# 09_FPGA_banks_5_6_7_8.net
KiCad netlist of a schematic drawn in Altium Designer
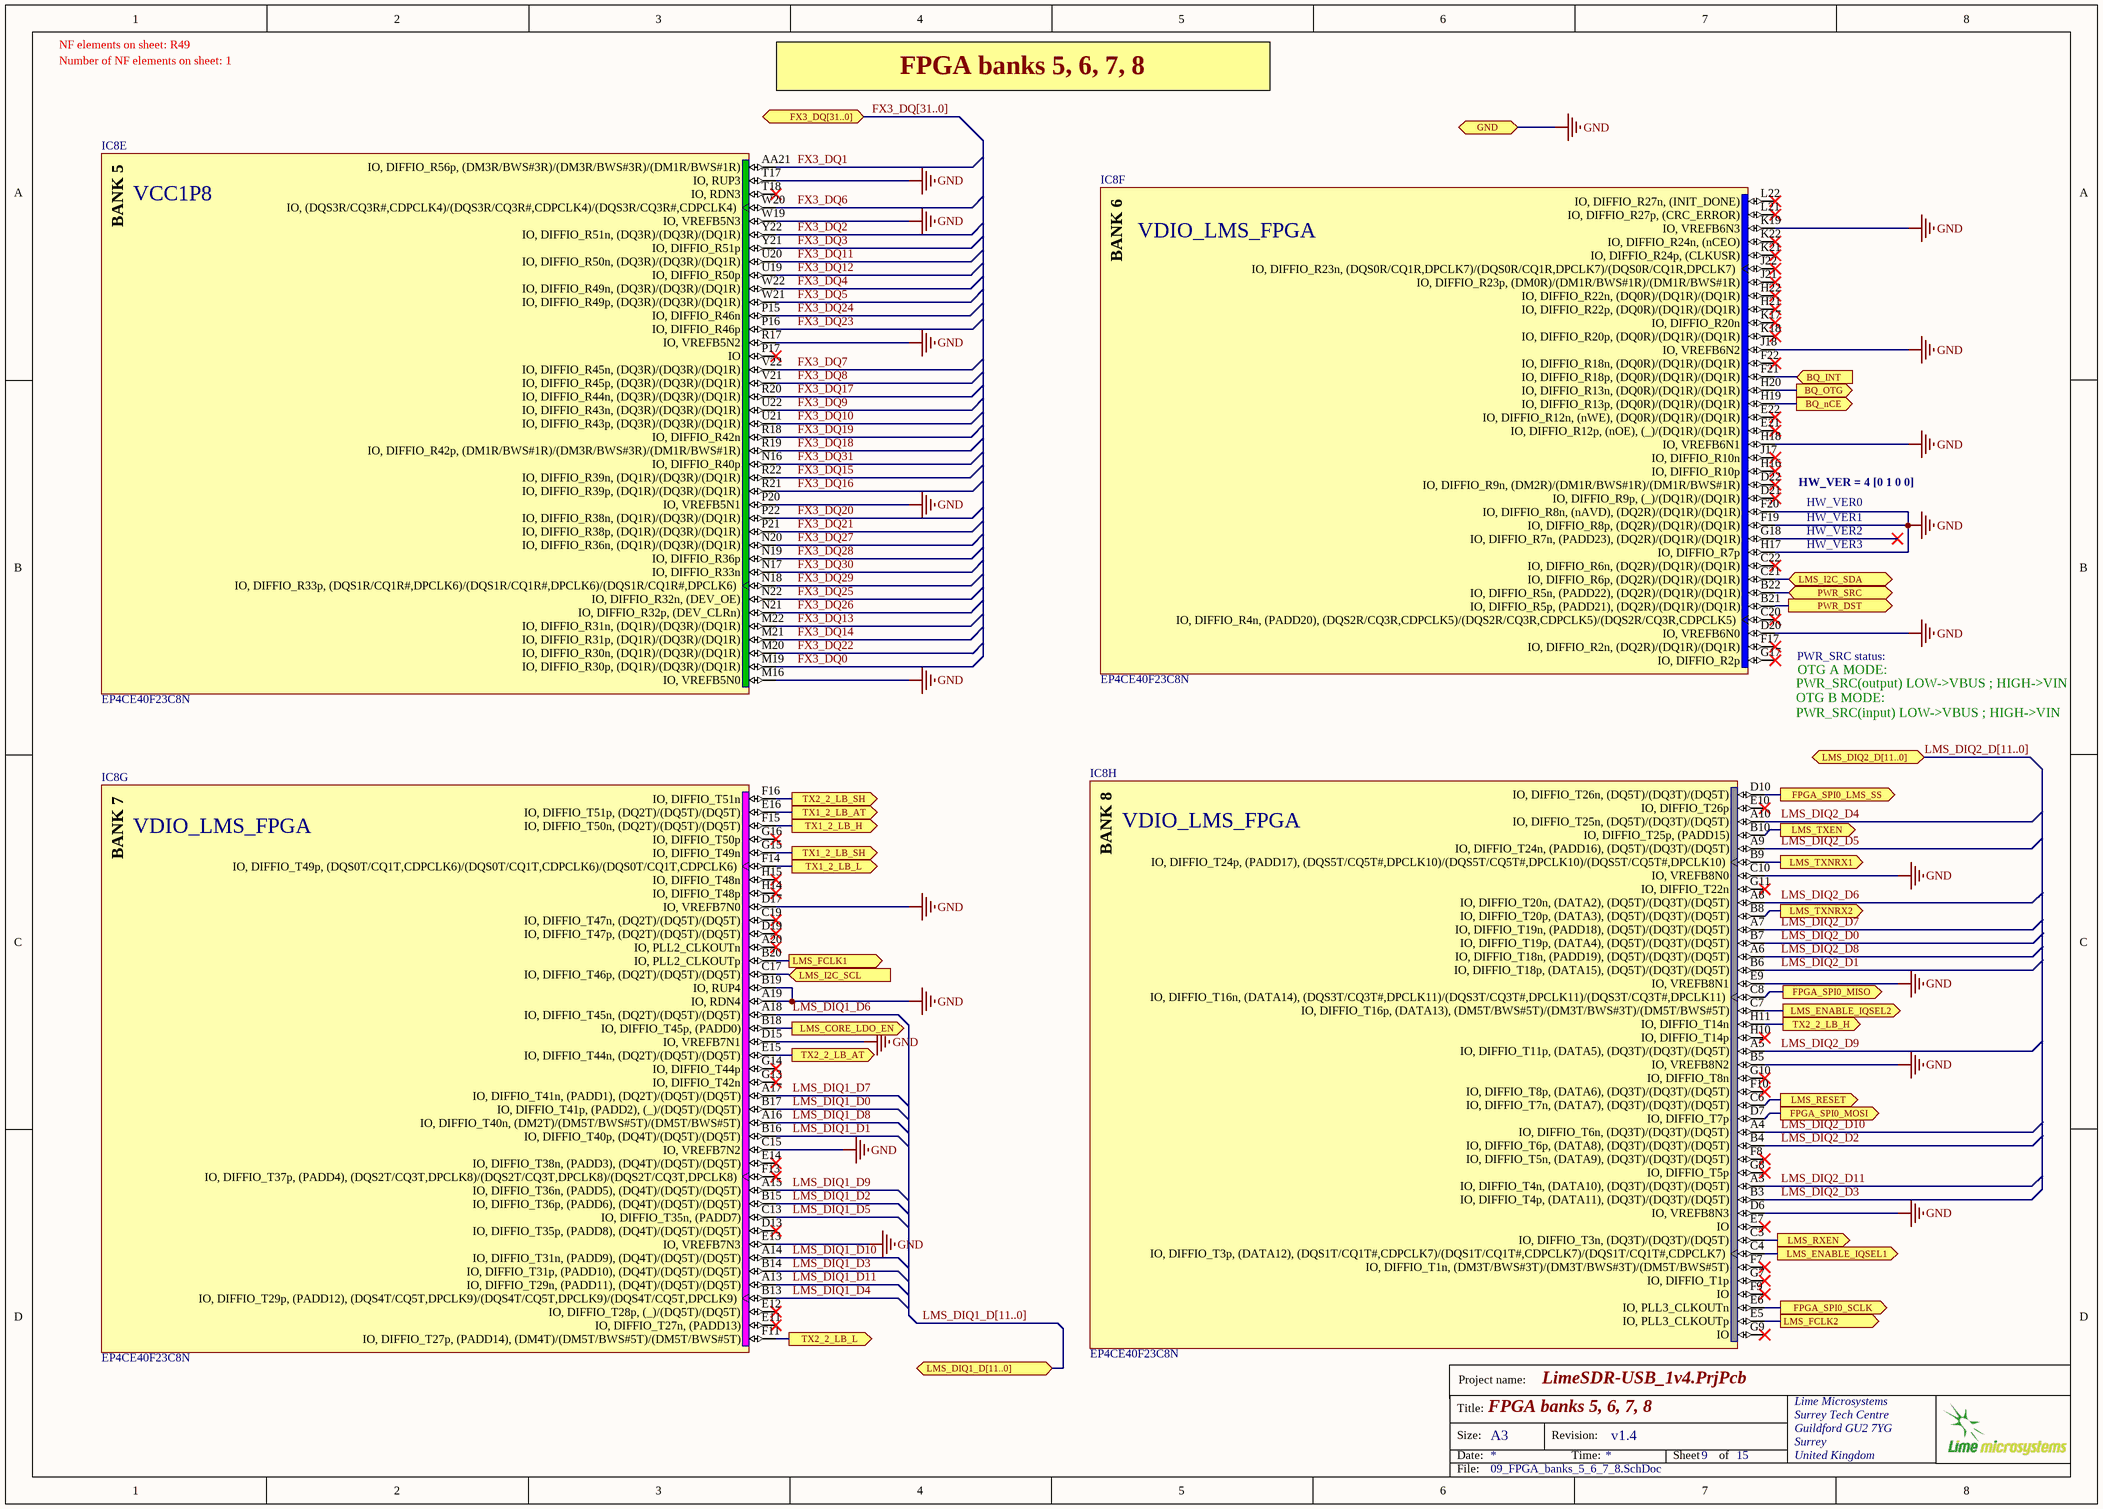
[diagram p0: 09_FPGA_banks_5_6_7_8.SchDoc]

(export (version "E")
  (design (tool "Eeschema 10.0.6"))
  (components
    (comp (ref "IC8")
      (value "EP4CE40F23C8N")
      (footprint "FBGA484_A-240")
      (description "IC FPGA 328 I/O 484FBGA")
      (fields (field (name "MANUFACTURER") "Altera"))
      (libsource (lib "LimeMicroAltiumLib_schLib") (part "EP4CE40F23C7N"))
    )
  )
  (nets
    (net (code "1") (name "/BQ_INT") (class "Default")
      (node (ref "IC8") (pin "F21") (pinfunction "IO,_DIFFIO_R18p,_(DQ0R)/(DQ1R)/(DQ1R)_F21") (pintype "bidirectional"))
    )
    (net (code "2") (name "/BQ_OTG") (class "Default")
      (node (ref "IC8") (pin "H20") (pinfunction "IO,_DIFFIO_R13n,_(DQ0R)/(DQ1R)/(DQ1R)_H20") (pintype "bidirectional"))
    )
    (net (code "3") (name "/BQ_nCE") (class "Default")
      (node (ref "IC8") (pin "H19") (pinfunction "IO,_DIFFIO_R13p,_(DQ0R)/(DQ1R)/(DQ1R)_H19") (pintype "bidirectional"))
    )
    (net (code "4") (name "/FPGA_SPI0_LMS_SS") (class "Default")
      (node (ref "IC8") (pin "D10") (pinfunction "IO,_DIFFIO_T26n,_(DQ5T)/(DQ3T)/(DQ5T)_D10") (pintype "bidirectional"))
    )
    (net (code "5") (name "/FPGA_SPI0_MISO") (class "Default")
      (node (ref "IC8") (pin "C8") (pinfunction "IO,_DIFFIO_T16n,_(DATA14),_(DQS3T/CQ3T#,DPCLK11)/(DQS3T/CQ3T#,DPCLK11)/(DQS3T/CQ3T#,DPCLK11)_C8") (pintype "bidirectional"))
    )
    (net (code "6") (name "/FPGA_SPI0_MOSI") (class "Default")
      (node (ref "IC8") (pin "D7") (pinfunction "IO,_DIFFIO_T7p_D7") (pintype "bidirectional"))
    )
    (net (code "7") (name "/FPGA_SPI0_SCLK") (class "Default")
      (node (ref "IC8") (pin "E6") (pinfunction "IO,_PLL3_CLKOUTn_E6") (pintype "bidirectional"))
    )
    (net (code "8") (name "/FX3_DQ0") (class "Default")
      (node (ref "IC8") (pin "M19") (pinfunction "IO,_DIFFIO_R30p,_(DQ1R)/(DQ3R)/(DQ1R)_M19") (pintype "bidirectional"))
    )
    (net (code "9") (name "/FX3_DQ1") (class "Default")
      (node (ref "IC8") (pin "AA21") (pinfunction "IO,_DIFFIO_R56p,_(DM3R/BWS#3R)/(DM3R/BWS#3R)/(DM1R/BWS#1R)_AA21") (pintype "bidirectional"))
    )
    (net (code "10") (name "/FX3_DQ2") (class "Default")
      (node (ref "IC8") (pin "Y22") (pinfunction "IO,_DIFFIO_R51n,_(DQ3R)/(DQ3R)/(DQ1R)_Y22") (pintype "bidirectional"))
    )
    (net (code "11") (name "/FX3_DQ3") (class "Default")
      (node (ref "IC8") (pin "Y21") (pinfunction "IO,_DIFFIO_R51p_Y21") (pintype "bidirectional"))
    )
    (net (code "12") (name "/FX3_DQ4") (class "Default")
      (node (ref "IC8") (pin "W22") (pinfunction "IO,_DIFFIO_R49n,_(DQ3R)/(DQ3R)/(DQ1R)_W22") (pintype "bidirectional"))
    )
    (net (code "13") (name "/FX3_DQ5") (class "Default")
      (node (ref "IC8") (pin "W21") (pinfunction "IO,_DIFFIO_R49p,_(DQ3R)/(DQ3R)/(DQ1R)_W21") (pintype "bidirectional"))
    )
    (net (code "14") (name "/FX3_DQ6") (class "Default")
      (node (ref "IC8") (pin "W20") (pinfunction "IO,_(DQS3R/CQ3R#,CDPCLK4)/(DQS3R/CQ3R#,CDPCLK4)/(DQS3R/CQ3R#,CDPCLK4)_W20") (pintype "bidirectional"))
    )
    (net (code "15") (name "/FX3_DQ7") (class "Default")
      (node (ref "IC8") (pin "V22") (pinfunction "IO,_DIFFIO_R45n,_(DQ3R)/(DQ3R)/(DQ1R)_V22") (pintype "bidirectional"))
    )
    (net (code "16") (name "/FX3_DQ8") (class "Default")
      (node (ref "IC8") (pin "V21") (pinfunction "IO,_DIFFIO_R45p,_(DQ3R)/(DQ3R)/(DQ1R)_V21") (pintype "bidirectional"))
    )
    (net (code "17") (name "/FX3_DQ9") (class "Default")
      (node (ref "IC8") (pin "U22") (pinfunction "IO,_DIFFIO_R43n,_(DQ3R)/(DQ3R)/(DQ1R)_U22") (pintype "bidirectional"))
    )
    (net (code "18") (name "/FX3_DQ10") (class "Default")
      (node (ref "IC8") (pin "U21") (pinfunction "IO,_DIFFIO_R43p,_(DQ3R)/(DQ3R)/(DQ1R)_U21") (pintype "bidirectional"))
    )
    (net (code "19") (name "/FX3_DQ11") (class "Default")
      (node (ref "IC8") (pin "U20") (pinfunction "IO,_DIFFIO_R50n,_(DQ3R)/(DQ3R)/(DQ1R)_U20") (pintype "bidirectional"))
    )
    (net (code "20") (name "/FX3_DQ12") (class "Default")
      (node (ref "IC8") (pin "U19") (pinfunction "IO,_DIFFIO_R50p_U19") (pintype "bidirectional"))
    )
    (net (code "21") (name "/FX3_DQ13") (class "Default")
      (node (ref "IC8") (pin "M22") (pinfunction "IO,_DIFFIO_R31n,_(DQ1R)/(DQ3R)/(DQ1R)_M22") (pintype "bidirectional"))
    )
    (net (code "22") (name "/FX3_DQ14") (class "Default")
      (node (ref "IC8") (pin "M21") (pinfunction "IO,_DIFFIO_R31p,_(DQ1R)/(DQ3R)/(DQ1R)_M21") (pintype "bidirectional"))
    )
    (net (code "23") (name "/FX3_DQ15") (class "Default")
      (node (ref "IC8") (pin "R22") (pinfunction "IO,_DIFFIO_R39n,_(DQ1R)/(DQ3R)/(DQ1R)_R22") (pintype "bidirectional"))
    )
    (net (code "24") (name "/FX3_DQ16") (class "Default")
      (node (ref "IC8") (pin "R21") (pinfunction "IO,_DIFFIO_R39p,_(DQ1R)/(DQ3R)/(DQ1R)_R21") (pintype "bidirectional"))
    )
    (net (code "25") (name "/FX3_DQ17") (class "Default")
      (node (ref "IC8") (pin "R20") (pinfunction "IO,_DIFFIO_R44n,_(DQ3R)/(DQ3R)/(DQ1R)_R20") (pintype "bidirectional"))
    )
    (net (code "26") (name "/FX3_DQ18") (class "Default")
      (node (ref "IC8") (pin "R19") (pinfunction "IO,_DIFFIO_R42p,_(DM1R/BWS#1R)/(DM3R/BWS#3R)/(DM1R/BWS#1R)_R19") (pintype "bidirectional"))
    )
    (net (code "27") (name "/FX3_DQ19") (class "Default")
      (node (ref "IC8") (pin "R18") (pinfunction "IO,_DIFFIO_R42n_R18") (pintype "bidirectional"))
    )
    (net (code "28") (name "/FX3_DQ20") (class "Default")
      (node (ref "IC8") (pin "P22") (pinfunction "IO,_DIFFIO_R38n,_(DQ1R)/(DQ3R)/(DQ1R)_P22") (pintype "bidirectional"))
    )
    (net (code "29") (name "/FX3_DQ21") (class "Default")
      (node (ref "IC8") (pin "P21") (pinfunction "IO,_DIFFIO_R38p,_(DQ1R)/(DQ3R)/(DQ1R)_P21") (pintype "bidirectional"))
    )
    (net (code "30") (name "/FX3_DQ22") (class "Default")
      (node (ref "IC8") (pin "M20") (pinfunction "IO,_DIFFIO_R30n,_(DQ1R)/(DQ3R)/(DQ1R)_M20") (pintype "bidirectional"))
    )
    (net (code "31") (name "/FX3_DQ23") (class "Default")
      (node (ref "IC8") (pin "P16") (pinfunction "IO,_DIFFIO_R46p_P16") (pintype "bidirectional"))
    )
    (net (code "32") (name "/FX3_DQ24") (class "Default")
      (node (ref "IC8") (pin "P15") (pinfunction "IO,_DIFFIO_R46n_P15") (pintype "bidirectional"))
    )
    (net (code "33") (name "/FX3_DQ25") (class "Default")
      (node (ref "IC8") (pin "N22") (pinfunction "IO,_DIFFIO_R32n,_(DEV_OE)_N22") (pintype "bidirectional"))
    )
    (net (code "34") (name "/FX3_DQ26") (class "Default")
      (node (ref "IC8") (pin "N21") (pinfunction "IO,_DIFFIO_R32p,_(DEV_CLRn)_N21") (pintype "bidirectional"))
    )
    (net (code "35") (name "/FX3_DQ27") (class "Default")
      (node (ref "IC8") (pin "N20") (pinfunction "IO,_DIFFIO_R36n,_(DQ1R)/(DQ3R)/(DQ1R)_N20") (pintype "bidirectional"))
    )
    (net (code "36") (name "/FX3_DQ28") (class "Default")
      (node (ref "IC8") (pin "N19") (pinfunction "IO,_DIFFIO_R36p_N19") (pintype "bidirectional"))
    )
    (net (code "37") (name "/FX3_DQ29") (class "Default")
      (node (ref "IC8") (pin "N18") (pinfunction "IO,_DIFFIO_R33p,_(DQS1R/CQ1R#,DPCLK6)/(DQS1R/CQ1R#,DPCLK6)/(DQS1R/CQ1R#,DPCLK6)_N18") (pintype "bidirectional"))
    )
    (net (code "38") (name "/FX3_DQ30") (class "Default")
      (node (ref "IC8") (pin "N17") (pinfunction "IO,_DIFFIO_R33n_N17") (pintype "bidirectional"))
    )
    (net (code "39") (name "/FX3_DQ31") (class "Default")
      (node (ref "IC8") (pin "N16") (pinfunction "IO,_DIFFIO_R40p_N16") (pintype "bidirectional"))
    )
    (net (code "41") (name "/LMS_CORE_LDO_EN") (class "Default")
      (node (ref "IC8") (pin "B18") (pinfunction "IO,_DIFFIO_T45p,_(PADD0)_B18") (pintype "bidirectional"))
    )
    (net (code "42") (name "/LMS_DIQ1_D0") (class "Default")
      (node (ref "IC8") (pin "B17") (pinfunction "IO,_DIFFIO_T41p,_(PADD2),_(_)/(DQ5T)/(DQ5T)_B17") (pintype "bidirectional"))
    )
    (net (code "43") (name "/LMS_DIQ1_D1") (class "Default")
      (node (ref "IC8") (pin "B16") (pinfunction "IO,_DIFFIO_T40p,_(DQ4T)/(DQ5T)/(DQ5T)_B16") (pintype "bidirectional"))
    )
    (net (code "44") (name "/LMS_DIQ1_D2") (class "Default")
      (node (ref "IC8") (pin "B15") (pinfunction "IO,_DIFFIO_T36p,_(PADD6),_(DQ4T)/(DQ5T)/(DQ5T)_B15") (pintype "bidirectional"))
    )
    (net (code "45") (name "/LMS_DIQ1_D3") (class "Default")
      (node (ref "IC8") (pin "B14") (pinfunction "IO,_DIFFIO_T31p,_(PADD10),_(DQ4T)/(DQ5T)/(DQ5T)_B14") (pintype "bidirectional"))
    )
    (net (code "46") (name "/LMS_DIQ1_D4") (class "Default")
      (node (ref "IC8") (pin "B13") (pinfunction "IO,_DIFFIO_T29p,_(PADD12),_(DQS4T/CQ5T,DPCLK9)/(DQS4T/CQ5T,DPCLK9)/(DQS4T/CQ5T,DPCLK9)_B13") (pintype "bidirectional"))
    )
    (net (code "47") (name "/LMS_DIQ1_D5") (class "Default")
      (node (ref "IC8") (pin "C13") (pinfunction "IO,_DIFFIO_T35n,_(PADD7)_C13") (pintype "bidirectional"))
    )
    (net (code "48") (name "/LMS_DIQ1_D6") (class "Default")
      (node (ref "IC8") (pin "A18") (pinfunction "IO,_DIFFIO_T45n,_(DQ2T)/(DQ5T)/(DQ5T)_A18") (pintype "bidirectional"))
    )
    (net (code "49") (name "/LMS_DIQ1_D7") (class "Default")
      (node (ref "IC8") (pin "A17") (pinfunction "IO,_DIFFIO_T41n,_(PADD1),_(DQ2T)/(DQ5T)/(DQ5T)_A17") (pintype "bidirectional"))
    )
    (net (code "50") (name "/LMS_DIQ1_D8") (class "Default")
      (node (ref "IC8") (pin "A16") (pinfunction "IO,_DIFFIO_T40n,_(DM2T)/(DM5T/BWS#5T)/(DM5T/BWS#5T)_A16") (pintype "bidirectional"))
    )
    (net (code "51") (name "/LMS_DIQ1_D9") (class "Default")
      (node (ref "IC8") (pin "A15") (pinfunction "IO,_DIFFIO_T36n,_(PADD5),_(DQ4T)/(DQ5T)/(DQ5T)_A15") (pintype "bidirectional"))
    )
    (net (code "52") (name "/LMS_DIQ1_D10") (class "Default")
      (node (ref "IC8") (pin "A14") (pinfunction "IO,_DIFFIO_T31n,_(PADD9),_(DQ4T)/(DQ5T)/(DQ5T)_A14") (pintype "bidirectional"))
    )
    (net (code "53") (name "/LMS_DIQ1_D11") (class "Default")
      (node (ref "IC8") (pin "A13") (pinfunction "IO,_DIFFIO_T29n,_(PADD11),_(DQ4T)/(DQ5T)/(DQ5T)_A13") (pintype "bidirectional"))
    )
    (net (code "55") (name "/LMS_DIQ2_D0") (class "Default")
      (node (ref "IC8") (pin "B7") (pinfunction "IO,_DIFFIO_T19p,_(DATA4),_(DQ5T)/(DQ3T)/(DQ5T)_B7") (pintype "bidirectional"))
    )
    (net (code "56") (name "/LMS_DIQ2_D1") (class "Default")
      (node (ref "IC8") (pin "B6") (pinfunction "IO,_DIFFIO_T18p,_(DATA15),_(DQ5T)/(DQ3T)/(DQ5T)_B6") (pintype "bidirectional"))
    )
    (net (code "57") (name "/LMS_DIQ2_D2") (class "Default")
      (node (ref "IC8") (pin "B4") (pinfunction "IO,_DIFFIO_T6p,_(DATA8),_(DQ3T)/(DQ3T)/(DQ5T)_B4") (pintype "bidirectional"))
    )
    (net (code "58") (name "/LMS_DIQ2_D3") (class "Default")
      (node (ref "IC8") (pin "B3") (pinfunction "IO,_DIFFIO_T4p,_(DATA11),_(DQ3T)/(DQ3T)/(DQ5T)_B3") (pintype "bidirectional"))
    )
    (net (code "59") (name "/LMS_DIQ2_D4") (class "Default")
      (node (ref "IC8") (pin "A10") (pinfunction "IO,_DIFFIO_T25n,_(DQ5T)/(DQ3T)/(DQ5T)_A10") (pintype "bidirectional"))
    )
    (net (code "60") (name "/LMS_DIQ2_D5") (class "Default")
      (node (ref "IC8") (pin "A9") (pinfunction "IO,_DIFFIO_T24n,_(PADD16),_(DQ5T)/(DQ3T)/(DQ5T)_A9") (pintype "bidirectional"))
    )
    (net (code "61") (name "/LMS_DIQ2_D6") (class "Default")
      (node (ref "IC8") (pin "A8") (pinfunction "IO,_DIFFIO_T20n,_(DATA2),_(DQ5T)/(DQ3T)/(DQ5T)_A8") (pintype "bidirectional"))
    )
    (net (code "62") (name "/LMS_DIQ2_D7") (class "Default")
      (node (ref "IC8") (pin "A7") (pinfunction "IO,_DIFFIO_T19n,_(PADD18),_(DQ5T)/(DQ3T)/(DQ5T)_A7") (pintype "bidirectional"))
    )
    (net (code "63") (name "/LMS_DIQ2_D8") (class "Default")
      (node (ref "IC8") (pin "A6") (pinfunction "IO,_DIFFIO_T18n,_(PADD19),_(DQ5T)/(DQ3T)/(DQ5T)_A6") (pintype "bidirectional"))
    )
    (net (code "64") (name "/LMS_DIQ2_D9") (class "Default")
      (node (ref "IC8") (pin "A5") (pinfunction "IO,_DIFFIO_T11p,_(DATA5),_(DQ3T)/(DQ3T)/(DQ5T)_A5") (pintype "bidirectional"))
    )
    (net (code "65") (name "/LMS_DIQ2_D10") (class "Default")
      (node (ref "IC8") (pin "A4") (pinfunction "IO,_DIFFIO_T6n,_(DQ3T)/(DQ3T)/(DQ5T)_A4") (pintype "bidirectional"))
    )
    (net (code "66") (name "/LMS_DIQ2_D11") (class "Default")
      (node (ref "IC8") (pin "A3") (pinfunction "IO,_DIFFIO_T4n,_(DATA10),_(DQ3T)/(DQ3T)/(DQ5T)_A3") (pintype "bidirectional"))
    )
    (net (code "68") (name "/LMS_ENABLE_IQSEL1") (class "Default")
      (node (ref "IC8") (pin "C4") (pinfunction "IO,_DIFFIO_T3p,_(DATA12),_(DQS1T/CQ1T#,CDPCLK7)/(DQS1T/CQ1T#,CDPCLK7)/(DQS1T/CQ1T#,CDPCLK7)_C4") (pintype "bidirectional"))
    )
    (net (code "69") (name "/LMS_ENABLE_IQSEL2") (class "Default")
      (node (ref "IC8") (pin "C7") (pinfunction "IO,_DIFFIO_T16p,_(DATA13),_(DM5T/BWS#5T)/(DM3T/BWS#3T)/(DM5T/BWS#5T)_C7") (pintype "bidirectional"))
    )
    (net (code "70") (name "/LMS_FCLK1") (class "Default")
      (node (ref "IC8") (pin "B20") (pinfunction "IO,_PLL2_CLKOUTp_B20") (pintype "bidirectional"))
    )
    (net (code "71") (name "/LMS_FCLK2") (class "Default")
      (node (ref "IC8") (pin "E5") (pinfunction "IO,_PLL3_CLKOUTp_E5") (pintype "bidirectional"))
    )
    (net (code "72") (name "/LMS_I2C_SCL") (class "Default")
      (node (ref "IC8") (pin "C17") (pinfunction "IO,_DIFFIO_T46p,_(DQ2T)/(DQ5T)/(DQ5T)_C17") (pintype "bidirectional"))
    )
    (net (code "73") (name "/LMS_I2C_SDA") (class "Default")
      (node (ref "IC8") (pin "C21") (pinfunction "IO,_DIFFIO_R6p,_(DQ2R)/(DQ1R)/(DQ1R)_C21") (pintype "bidirectional"))
    )
    (net (code "74") (name "/LMS_RESET") (class "Default")
      (node (ref "IC8") (pin "C6") (pinfunction "IO,_DIFFIO_T7n,_(DATA7),_(DQ3T)/(DQ3T)/(DQ5T)_C6") (pintype "bidirectional"))
    )
    (net (code "75") (name "/LMS_RXEN") (class "Default")
      (node (ref "IC8") (pin "C3") (pinfunction "IO,_DIFFIO_T3n,_(DQ3T)/(DQ3T)/(DQ5T)_C3") (pintype "bidirectional"))
    )
    (net (code "76") (name "/LMS_TXEN") (class "Default")
      (node (ref "IC8") (pin "B10") (pinfunction "IO,_DIFFIO_T25p,_(PADD15)_B10") (pintype "bidirectional"))
    )
    (net (code "77") (name "/LMS_TXNRX1") (class "Default")
      (node (ref "IC8") (pin "B9") (pinfunction "IO,_DIFFIO_T24p,_(PADD17),_(DQS5T/CQ5T#,DPCLK10)/(DQS5T/CQ5T#,DPCLK10)/(DQS5T/CQ5T#,DPCLK10)_B9") (pintype "bidirectional"))
    )
    (net (code "78") (name "/LMS_TXNRX2") (class "Default")
      (node (ref "IC8") (pin "B8") (pinfunction "IO,_DIFFIO_T20p,_(DATA3),_(DQ5T)/(DQ3T)/(DQ5T)_B8") (pintype "bidirectional"))
    )
    (net (code "79") (name "/PWR_DST") (class "Default")
      (node (ref "IC8") (pin "B21") (pinfunction "IO,_DIFFIO_R5p,_(PADD21),_(DQ2R)/(DQ1R)/(DQ1R)_B21") (pintype "bidirectional"))
    )
    (net (code "80") (name "/PWR_SRC") (class "Default")
      (node (ref "IC8") (pin "B22") (pinfunction "IO,_DIFFIO_R5n,_(PADD22),_(DQ2R)/(DQ1R)/(DQ1R)_B22") (pintype "bidirectional"))
    )
    (net (code "81") (name "/TX1_2_LB_AT") (class "Default")
      (node (ref "IC8") (pin "E16") (pinfunction "IO,_DIFFIO_T51p,_(DQ2T)/(DQ5T)/(DQ5T)_E16") (pintype "bidirectional"))
    )
    (net (code "82") (name "/TX1_2_LB_H") (class "Default")
      (node (ref "IC8") (pin "F15") (pinfunction "IO,_DIFFIO_T50n,_(DQ2T)/(DQ5T)/(DQ5T)_F15") (pintype "bidirectional"))
    )
    (net (code "83") (name "/TX1_2_LB_L") (class "Default")
      (node (ref "IC8") (pin "F14") (pinfunction "IO,_DIFFIO_T49p,_(DQS0T/CQ1T,CDPCLK6)/(DQS0T/CQ1T,CDPCLK6)/(DQS0T/CQ1T,CDPCLK6)_F14") (pintype "bidirectional"))
    )
    (net (code "84") (name "/TX1_2_LB_SH") (class "Default")
      (node (ref "IC8") (pin "G15") (pinfunction "IO,_DIFFIO_T49n_G15") (pintype "bidirectional"))
    )
    (net (code "85") (name "/TX2_2_LB_AT") (class "Default")
      (node (ref "IC8") (pin "E15") (pinfunction "IO,_DIFFIO_T44n,_(DQ2T)/(DQ5T)/(DQ5T)_E15") (pintype "bidirectional"))
    )
    (net (code "86") (name "/TX2_2_LB_H") (class "Default")
      (node (ref "IC8") (pin "H11") (pinfunction "IO,_DIFFIO_T14n_H11") (pintype "bidirectional"))
    )
    (net (code "87") (name "/TX2_2_LB_L") (class "Default")
      (node (ref "IC8") (pin "F11") (pinfunction "IO,_DIFFIO_T27p,_(PADD14),_(DM4T)/(DM5T/BWS#5T)/(DM5T/BWS#5T)_F11") (pintype "bidirectional"))
    )
    (net (code "88") (name "/TX2_2_LB_SH") (class "Default")
      (node (ref "IC8") (pin "F16") (pinfunction "IO,_DIFFIO_T51n_F16") (pintype "bidirectional"))
    )
    (net (code "89") (name "GND") (class "Default")
      (node (ref "IC8") (pin "A19") (pinfunction "IO,_RDN4_A19") (pintype "bidirectional"))
      (node (ref "IC8") (pin "B19") (pinfunction "IO,_RUP4_B19") (pintype "bidirectional"))
      (node (ref "IC8") (pin "B5") (pinfunction "IO,_VREFB8N2_B5") (pintype "bidirectional"))
      (node (ref "IC8") (pin "C10") (pinfunction "IO,_VREFB8N0_C10") (pintype "bidirectional"))
      (node (ref "IC8") (pin "C15") (pinfunction "IO,_VREFB7N2_C15") (pintype "bidirectional"))
      (node (ref "IC8") (pin "D15") (pinfunction "IO,_VREFB7N1_D15") (pintype "bidirectional"))
      (node (ref "IC8") (pin "D17") (pinfunction "IO,_VREFB7N0_D17") (pintype "bidirectional"))
      (node (ref "IC8") (pin "D20") (pinfunction "IO,_VREFB6N0_D20") (pintype "bidirectional"))
      (node (ref "IC8") (pin "D6") (pinfunction "IO,_VREFB8N3_D6") (pintype "bidirectional"))
      (node (ref "IC8") (pin "E13") (pinfunction "IO,_VREFB7N3_E13") (pintype "bidirectional"))
      (node (ref "IC8") (pin "E9") (pinfunction "IO,_VREFB8N1_E9") (pintype "bidirectional"))
      (node (ref "IC8") (pin "F19") (pinfunction "IO,_DIFFIO_R8p,_(DQ2R)/(DQ1R)/(DQ1R)_F19") (pintype "bidirectional"))
      (node (ref "IC8") (pin "F20") (pinfunction "IO,_DIFFIO_R8n,_(nAVD),_(DQ2R)/(DQ1R)/(DQ1R)_F20") (pintype "bidirectional"))
      (node (ref "IC8") (pin "H17") (pinfunction "IO,_DIFFIO_R7p_H17") (pintype "bidirectional"))
      (node (ref "IC8") (pin "H18") (pinfunction "IO,_VREFB6N1_H18") (pintype "bidirectional"))
      (node (ref "IC8") (pin "J18") (pinfunction "IO,_VREFB6N2_J18") (pintype "bidirectional"))
      (node (ref "IC8") (pin "K19") (pinfunction "IO,_VREFB6N3_K19") (pintype "bidirectional"))
      (node (ref "IC8") (pin "M16") (pinfunction "IO,_VREFB5N0_M16") (pintype "bidirectional"))
      (node (ref "IC8") (pin "P20") (pinfunction "IO,_VREFB5N1_P20") (pintype "bidirectional"))
      (node (ref "IC8") (pin "R17") (pinfunction "IO,_VREFB5N2_R17") (pintype "bidirectional"))
      (node (ref "IC8") (pin "T17") (pinfunction "IO,_RUP3_T17") (pintype "bidirectional"))
      (node (ref "IC8") (pin "W19") (pinfunction "IO,_VREFB5N3_W19") (pintype "bidirectional"))
    )
    (net (code "90") (name "unconnected-(IC8E-IO,_RDN3-PadT18)") (class "Default")
      (node (ref "IC8") (pin "T18") (pinfunction "IO,_RDN3_T18") (pintype "bidirectional+no_connect"))
    )
    (net (code "91") (name "unconnected-(IC8E-IO-PadP17)") (class "Default")
      (node (ref "IC8") (pin "P17") (pinfunction "IO_P17") (pintype "bidirectional+no_connect"))
    )
    (net (code "92") (name "unconnected-(IC8F-IO,_DIFFIO_R2n,_(DQ2R){slash}(DQ1R){slash}(DQ1R)-PadF17)") (class "Default")
      (node (ref "IC8") (pin "F17") (pinfunction "IO,_DIFFIO_R2n,_(DQ2R)/(DQ1R)/(DQ1R)_F17") (pintype "bidirectional+no_connect"))
    )
    (net (code "93") (name "unconnected-(IC8F-IO,_DIFFIO_R2p-PadG17)") (class "Default")
      (node (ref "IC8") (pin "G17") (pinfunction "IO,_DIFFIO_R2p_G17") (pintype "bidirectional+no_connect"))
    )
    (net (code "94") (name "unconnected-(IC8F-IO,_DIFFIO_R4n,_(PADD20),_(DQS2R{slash}CQ3R,CDPCLK5){slash}(DQS2R{slash}CQ3R,CDPCLK5){slash}(DQS2R{slash}CQ3R,CDPCLK5)-PadC20)") (class "Default")
      (node (ref "IC8") (pin "C20") (pinfunction "IO,_DIFFIO_R4n,_(PADD20),_(DQS2R/CQ3R,CDPCLK5)/(DQS2R/CQ3R,CDPCLK5)/(DQS2R/CQ3R,CDPCLK5)_C20") (pintype "bidirectional+no_connect"))
    )
    (net (code "95") (name "unconnected-(IC8F-IO,_DIFFIO_R6n,_(DQ2R){slash}(DQ1R){slash}(DQ1R)-PadC22)") (class "Default")
      (node (ref "IC8") (pin "C22") (pinfunction "IO,_DIFFIO_R6n,_(DQ2R)/(DQ1R)/(DQ1R)_C22") (pintype "bidirectional+no_connect"))
    )
    (net (code "96") (name "unconnected-(IC8F-IO,_DIFFIO_R7n,_(PADD23),_(DQ2R){slash}(DQ1R){slash}(DQ1R)-PadG18)") (class "Default")
      (node (ref "IC8") (pin "G18") (pinfunction "IO,_DIFFIO_R7n,_(PADD23),_(DQ2R)/(DQ1R)/(DQ1R)_G18") (pintype "bidirectional+no_connect"))
    )
    (net (code "97") (name "unconnected-(IC8F-IO,_DIFFIO_R9n,_(DM2R){slash}(DM1R{slash}BWS#1R){slash}(DM1R{slash}BWS#1R)-PadD22)") (class "Default")
      (node (ref "IC8") (pin "D22") (pinfunction "IO,_DIFFIO_R9n,_(DM2R)/(DM1R/BWS#1R)/(DM1R/BWS#1R)_D22") (pintype "bidirectional+no_connect"))
    )
    (net (code "98") (name "unconnected-(IC8F-IO,_DIFFIO_R9p,_(_){slash}(DQ1R){slash}(DQ1R)-PadD21)") (class "Default")
      (node (ref "IC8") (pin "D21") (pinfunction "IO,_DIFFIO_R9p,_(_)/(DQ1R)/(DQ1R)_D21") (pintype "bidirectional+no_connect"))
    )
    (net (code "99") (name "unconnected-(IC8F-IO,_DIFFIO_R10n-PadJ17)") (class "Default")
      (node (ref "IC8") (pin "J17") (pinfunction "IO,_DIFFIO_R10n_J17") (pintype "bidirectional+no_connect"))
    )
    (net (code "100") (name "unconnected-(IC8F-IO,_DIFFIO_R10p-PadH16)") (class "Default")
      (node (ref "IC8") (pin "H16") (pinfunction "IO,_DIFFIO_R10p_H16") (pintype "bidirectional+no_connect"))
    )
    (net (code "101") (name "unconnected-(IC8F-IO,_DIFFIO_R12n,_(nWE),_(DQ0R){slash}(DQ1R){slash}(DQ1R)-PadE22)") (class "Default")
      (node (ref "IC8") (pin "E22") (pinfunction "IO,_DIFFIO_R12n,_(nWE),_(DQ0R)/(DQ1R)/(DQ1R)_E22") (pintype "bidirectional+no_connect"))
    )
    (net (code "102") (name "unconnected-(IC8F-IO,_DIFFIO_R12p,_(nOE),_(_){slash}(DQ1R){slash}(DQ1R)-PadE21)") (class "Default")
      (node (ref "IC8") (pin "E21") (pinfunction "IO,_DIFFIO_R12p,_(nOE),_(_)/(DQ1R)/(DQ1R)_E21") (pintype "bidirectional+no_connect"))
    )
    (net (code "103") (name "unconnected-(IC8F-IO,_DIFFIO_R18n,_(DQ0R){slash}(DQ1R){slash}(DQ1R)-PadF22)") (class "Default")
      (node (ref "IC8") (pin "F22") (pinfunction "IO,_DIFFIO_R18n,_(DQ0R)/(DQ1R)/(DQ1R)_F22") (pintype "bidirectional+no_connect"))
    )
    (net (code "104") (name "unconnected-(IC8F-IO,_DIFFIO_R20n-PadK17)") (class "Default")
      (node (ref "IC8") (pin "K17") (pinfunction "IO,_DIFFIO_R20n_K17") (pintype "bidirectional+no_connect"))
    )
    (net (code "105") (name "unconnected-(IC8F-IO,_DIFFIO_R20p,_(DQ0R){slash}(DQ1R){slash}(DQ1R)-PadK18)") (class "Default")
      (node (ref "IC8") (pin "K18") (pinfunction "IO,_DIFFIO_R20p,_(DQ0R)/(DQ1R)/(DQ1R)_K18") (pintype "bidirectional+no_connect"))
    )
    (net (code "106") (name "unconnected-(IC8F-IO,_DIFFIO_R22n,_(DQ0R){slash}(DQ1R){slash}(DQ1R)-PadH22)") (class "Default")
      (node (ref "IC8") (pin "H22") (pinfunction "IO,_DIFFIO_R22n,_(DQ0R)/(DQ1R)/(DQ1R)_H22") (pintype "bidirectional+no_connect"))
    )
    (net (code "107") (name "unconnected-(IC8F-IO,_DIFFIO_R22p,_(DQ0R){slash}(DQ1R){slash}(DQ1R)-PadH21)") (class "Default")
      (node (ref "IC8") (pin "H21") (pinfunction "IO,_DIFFIO_R22p,_(DQ0R)/(DQ1R)/(DQ1R)_H21") (pintype "bidirectional+no_connect"))
    )
    (net (code "108") (name "unconnected-(IC8F-IO,_DIFFIO_R23n,_(DQS0R{slash}CQ1R,DPCLK7){slash}(DQS0R{slash}CQ1R,DPCLK7){slash}(DQS0R{slash}CQ1R,DPCLK7)-PadJ22)") (class "Default")
      (node (ref "IC8") (pin "J22") (pinfunction "IO,_DIFFIO_R23n,_(DQS0R/CQ1R,DPCLK7)/(DQS0R/CQ1R,DPCLK7)/(DQS0R/CQ1R,DPCLK7)_J22") (pintype "bidirectional+no_connect"))
    )
    (net (code "109") (name "unconnected-(IC8F-IO,_DIFFIO_R23p,_(DM0R){slash}(DM1R{slash}BWS#1R){slash}(DM1R{slash}BWS#1R)-PadJ21)") (class "Default")
      (node (ref "IC8") (pin "J21") (pinfunction "IO,_DIFFIO_R23p,_(DM0R)/(DM1R/BWS#1R)/(DM1R/BWS#1R)_J21") (pintype "bidirectional+no_connect"))
    )
    (net (code "110") (name "unconnected-(IC8F-IO,_DIFFIO_R24n,_(nCEO)-PadK22)") (class "Default")
      (node (ref "IC8") (pin "K22") (pinfunction "IO,_DIFFIO_R24n,_(nCEO)_K22") (pintype "bidirectional+no_connect"))
    )
    (net (code "111") (name "unconnected-(IC8F-IO,_DIFFIO_R24p,_(CLKUSR)-PadK21)") (class "Default")
      (node (ref "IC8") (pin "K21") (pinfunction "IO,_DIFFIO_R24p,_(CLKUSR)_K21") (pintype "bidirectional+no_connect"))
    )
    (net (code "112") (name "unconnected-(IC8F-IO,_DIFFIO_R27n,_(INIT_DONE)-PadL22)") (class "Default")
      (node (ref "IC8") (pin "L22") (pinfunction "IO,_DIFFIO_R27n,_(INIT_DONE)_L22") (pintype "bidirectional+no_connect"))
    )
    (net (code "113") (name "unconnected-(IC8F-IO,_DIFFIO_R27p,_(CRC_ERROR)-PadL21)") (class "Default")
      (node (ref "IC8") (pin "L21") (pinfunction "IO,_DIFFIO_R27p,_(CRC_ERROR)_L21") (pintype "bidirectional+no_connect"))
    )
    (net (code "114") (name "unconnected-(IC8G-IO,_DIFFIO_T27n,_(PADD13)-PadE11)") (class "Default")
      (node (ref "IC8") (pin "E11") (pinfunction "IO,_DIFFIO_T27n,_(PADD13)_E11") (pintype "bidirectional+no_connect"))
    )
    (net (code "115") (name "unconnected-(IC8G-IO,_DIFFIO_T28p,_(_){slash}(DQ5T){slash}(DQ5T)-PadE12)") (class "Default")
      (node (ref "IC8") (pin "E12") (pinfunction "IO,_DIFFIO_T28p,_(_)/(DQ5T)/(DQ5T)_E12") (pintype "bidirectional+no_connect"))
    )
    (net (code "116") (name "unconnected-(IC8G-IO,_DIFFIO_T35p,_(PADD8),_(DQ4T){slash}(DQ5T){slash}(DQ5T)-PadD13)") (class "Default")
      (node (ref "IC8") (pin "D13") (pinfunction "IO,_DIFFIO_T35p,_(PADD8),_(DQ4T)/(DQ5T)/(DQ5T)_D13") (pintype "bidirectional+no_connect"))
    )
    (net (code "117") (name "unconnected-(IC8G-IO,_DIFFIO_T37p,_(PADD4),_(DQS2T{slash}CQ3T,DPCLK8){slash}(DQS2T{slash}CQ3T,DPCLK8){slash}(DQS2T{slash}CQ3T,DPCLK8)-PadF13)") (class "Default")
      (node (ref "IC8") (pin "F13") (pinfunction "IO,_DIFFIO_T37p,_(PADD4),_(DQS2T/CQ3T,DPCLK8)/(DQS2T/CQ3T,DPCLK8)/(DQS2T/CQ3T,DPCLK8)_F13") (pintype "bidirectional+no_connect"))
    )
    (net (code "118") (name "unconnected-(IC8G-IO,_DIFFIO_T38n,_(PADD3),_(DQ4T){slash}(DQ5T){slash}(DQ5T)-PadE14)") (class "Default")
      (node (ref "IC8") (pin "E14") (pinfunction "IO,_DIFFIO_T38n,_(PADD3),_(DQ4T)/(DQ5T)/(DQ5T)_E14") (pintype "bidirectional+no_connect"))
    )
    (net (code "119") (name "unconnected-(IC8G-IO,_DIFFIO_T42n-PadG13)") (class "Default")
      (node (ref "IC8") (pin "G13") (pinfunction "IO,_DIFFIO_T42n_G13") (pintype "bidirectional+no_connect"))
    )
    (net (code "120") (name "unconnected-(IC8G-IO,_DIFFIO_T44p-PadG14)") (class "Default")
      (node (ref "IC8") (pin "G14") (pinfunction "IO,_DIFFIO_T44p_G14") (pintype "bidirectional+no_connect"))
    )
    (net (code "121") (name "unconnected-(IC8G-IO,_DIFFIO_T47n,_(DQ2T){slash}(DQ5T){slash}(DQ5T)-PadC19)") (class "Default")
      (node (ref "IC8") (pin "C19") (pinfunction "IO,_DIFFIO_T47n,_(DQ2T)/(DQ5T)/(DQ5T)_C19") (pintype "bidirectional+no_connect"))
    )
    (net (code "122") (name "unconnected-(IC8G-IO,_DIFFIO_T47p,_(DQ2T){slash}(DQ5T){slash}(DQ5T)-PadD19)") (class "Default")
      (node (ref "IC8") (pin "D19") (pinfunction "IO,_DIFFIO_T47p,_(DQ2T)/(DQ5T)/(DQ5T)_D19") (pintype "bidirectional+no_connect"))
    )
    (net (code "123") (name "unconnected-(IC8G-IO,_DIFFIO_T48n-PadH15)") (class "Default")
      (node (ref "IC8") (pin "H15") (pinfunction "IO,_DIFFIO_T48n_H15") (pintype "bidirectional+no_connect"))
    )
    (net (code "124") (name "unconnected-(IC8G-IO,_DIFFIO_T48p-PadH14)") (class "Default")
      (node (ref "IC8") (pin "H14") (pinfunction "IO,_DIFFIO_T48p_H14") (pintype "bidirectional+no_connect"))
    )
    (net (code "125") (name "unconnected-(IC8G-IO,_DIFFIO_T50p-PadG16)") (class "Default")
      (node (ref "IC8") (pin "G16") (pinfunction "IO,_DIFFIO_T50p_G16") (pintype "bidirectional+no_connect"))
    )
    (net (code "126") (name "unconnected-(IC8G-IO,_PLL2_CLKOUTn-PadA20)") (class "Default")
      (node (ref "IC8") (pin "A20") (pinfunction "IO,_PLL2_CLKOUTn_A20") (pintype "bidirectional+no_connect"))
    )
    (net (code "127") (name "unconnected-(IC8H-IO,_DIFFIO_T1n,_(DM3T{slash}BWS#3T){slash}(DM3T{slash}BWS#3T){slash}(DM5T{slash}BWS#5T)-PadF7)") (class "Default")
      (node (ref "IC8") (pin "F7") (pinfunction "IO,_DIFFIO_T1n,_(DM3T/BWS#3T)/(DM3T/BWS#3T)/(DM5T/BWS#5T)_F7") (pintype "bidirectional+no_connect"))
    )
    (net (code "128") (name "unconnected-(IC8H-IO,_DIFFIO_T1p-PadG7)") (class "Default")
      (node (ref "IC8") (pin "G7") (pinfunction "IO,_DIFFIO_T1p_G7") (pintype "bidirectional+no_connect"))
    )
    (net (code "129") (name "unconnected-(IC8H-IO,_DIFFIO_T5n,_(DATA9),_(DQ3T){slash}(DQ3T){slash}(DQ5T)-PadF8)") (class "Default")
      (node (ref "IC8") (pin "F8") (pinfunction "IO,_DIFFIO_T5n,_(DATA9),_(DQ3T)/(DQ3T)/(DQ5T)_F8") (pintype "bidirectional+no_connect"))
    )
    (net (code "130") (name "unconnected-(IC8H-IO,_DIFFIO_T5p-PadG8)") (class "Default")
      (node (ref "IC8") (pin "G8") (pinfunction "IO,_DIFFIO_T5p_G8") (pintype "bidirectional+no_connect"))
    )
    (net (code "131") (name "unconnected-(IC8H-IO,_DIFFIO_T8n-PadG10)") (class "Default")
      (node (ref "IC8") (pin "G10") (pinfunction "IO,_DIFFIO_T8n_G10") (pintype "bidirectional+no_connect"))
    )
    (net (code "132") (name "unconnected-(IC8H-IO,_DIFFIO_T8p,_(DATA6),_(DQ3T){slash}(DQ3T){slash}(DQ5T)-PadF10)") (class "Default")
      (node (ref "IC8") (pin "F10") (pinfunction "IO,_DIFFIO_T8p,_(DATA6),_(DQ3T)/(DQ3T)/(DQ5T)_F10") (pintype "bidirectional+no_connect"))
    )
    (net (code "133") (name "unconnected-(IC8H-IO,_DIFFIO_T14p-PadH10)") (class "Default")
      (node (ref "IC8") (pin "H10") (pinfunction "IO,_DIFFIO_T14p_H10") (pintype "bidirectional+no_connect"))
    )
    (net (code "134") (name "unconnected-(IC8H-IO,_DIFFIO_T22n-PadG11)") (class "Default")
      (node (ref "IC8") (pin "G11") (pinfunction "IO,_DIFFIO_T22n_G11") (pintype "bidirectional+no_connect"))
    )
    (net (code "135") (name "unconnected-(IC8H-IO,_DIFFIO_T26p-PadE10)") (class "Default")
      (node (ref "IC8") (pin "E10") (pinfunction "IO,_DIFFIO_T26p_E10") (pintype "bidirectional+no_connect"))
    )
    (net (code "136") (name "unconnected-(IC8H-IO-PadE7)") (class "Default")
      (node (ref "IC8") (pin "E7") (pinfunction "IO_E7") (pintype "bidirectional+no_connect"))
    )
    (net (code "137") (name "unconnected-(IC8H-IO-PadF9)") (class "Default")
      (node (ref "IC8") (pin "F9") (pinfunction "IO_F9") (pintype "bidirectional+no_connect"))
    )
    (net (code "138") (name "unconnected-(IC8H-IO-PadG9)") (class "Default")
      (node (ref "IC8") (pin "G9") (pinfunction "IO_G9") (pintype "bidirectional+no_connect"))
    )
  )
)
